# F1C100S-MY-.net
KiCad netlist of a schematic drawn in Altium Designer
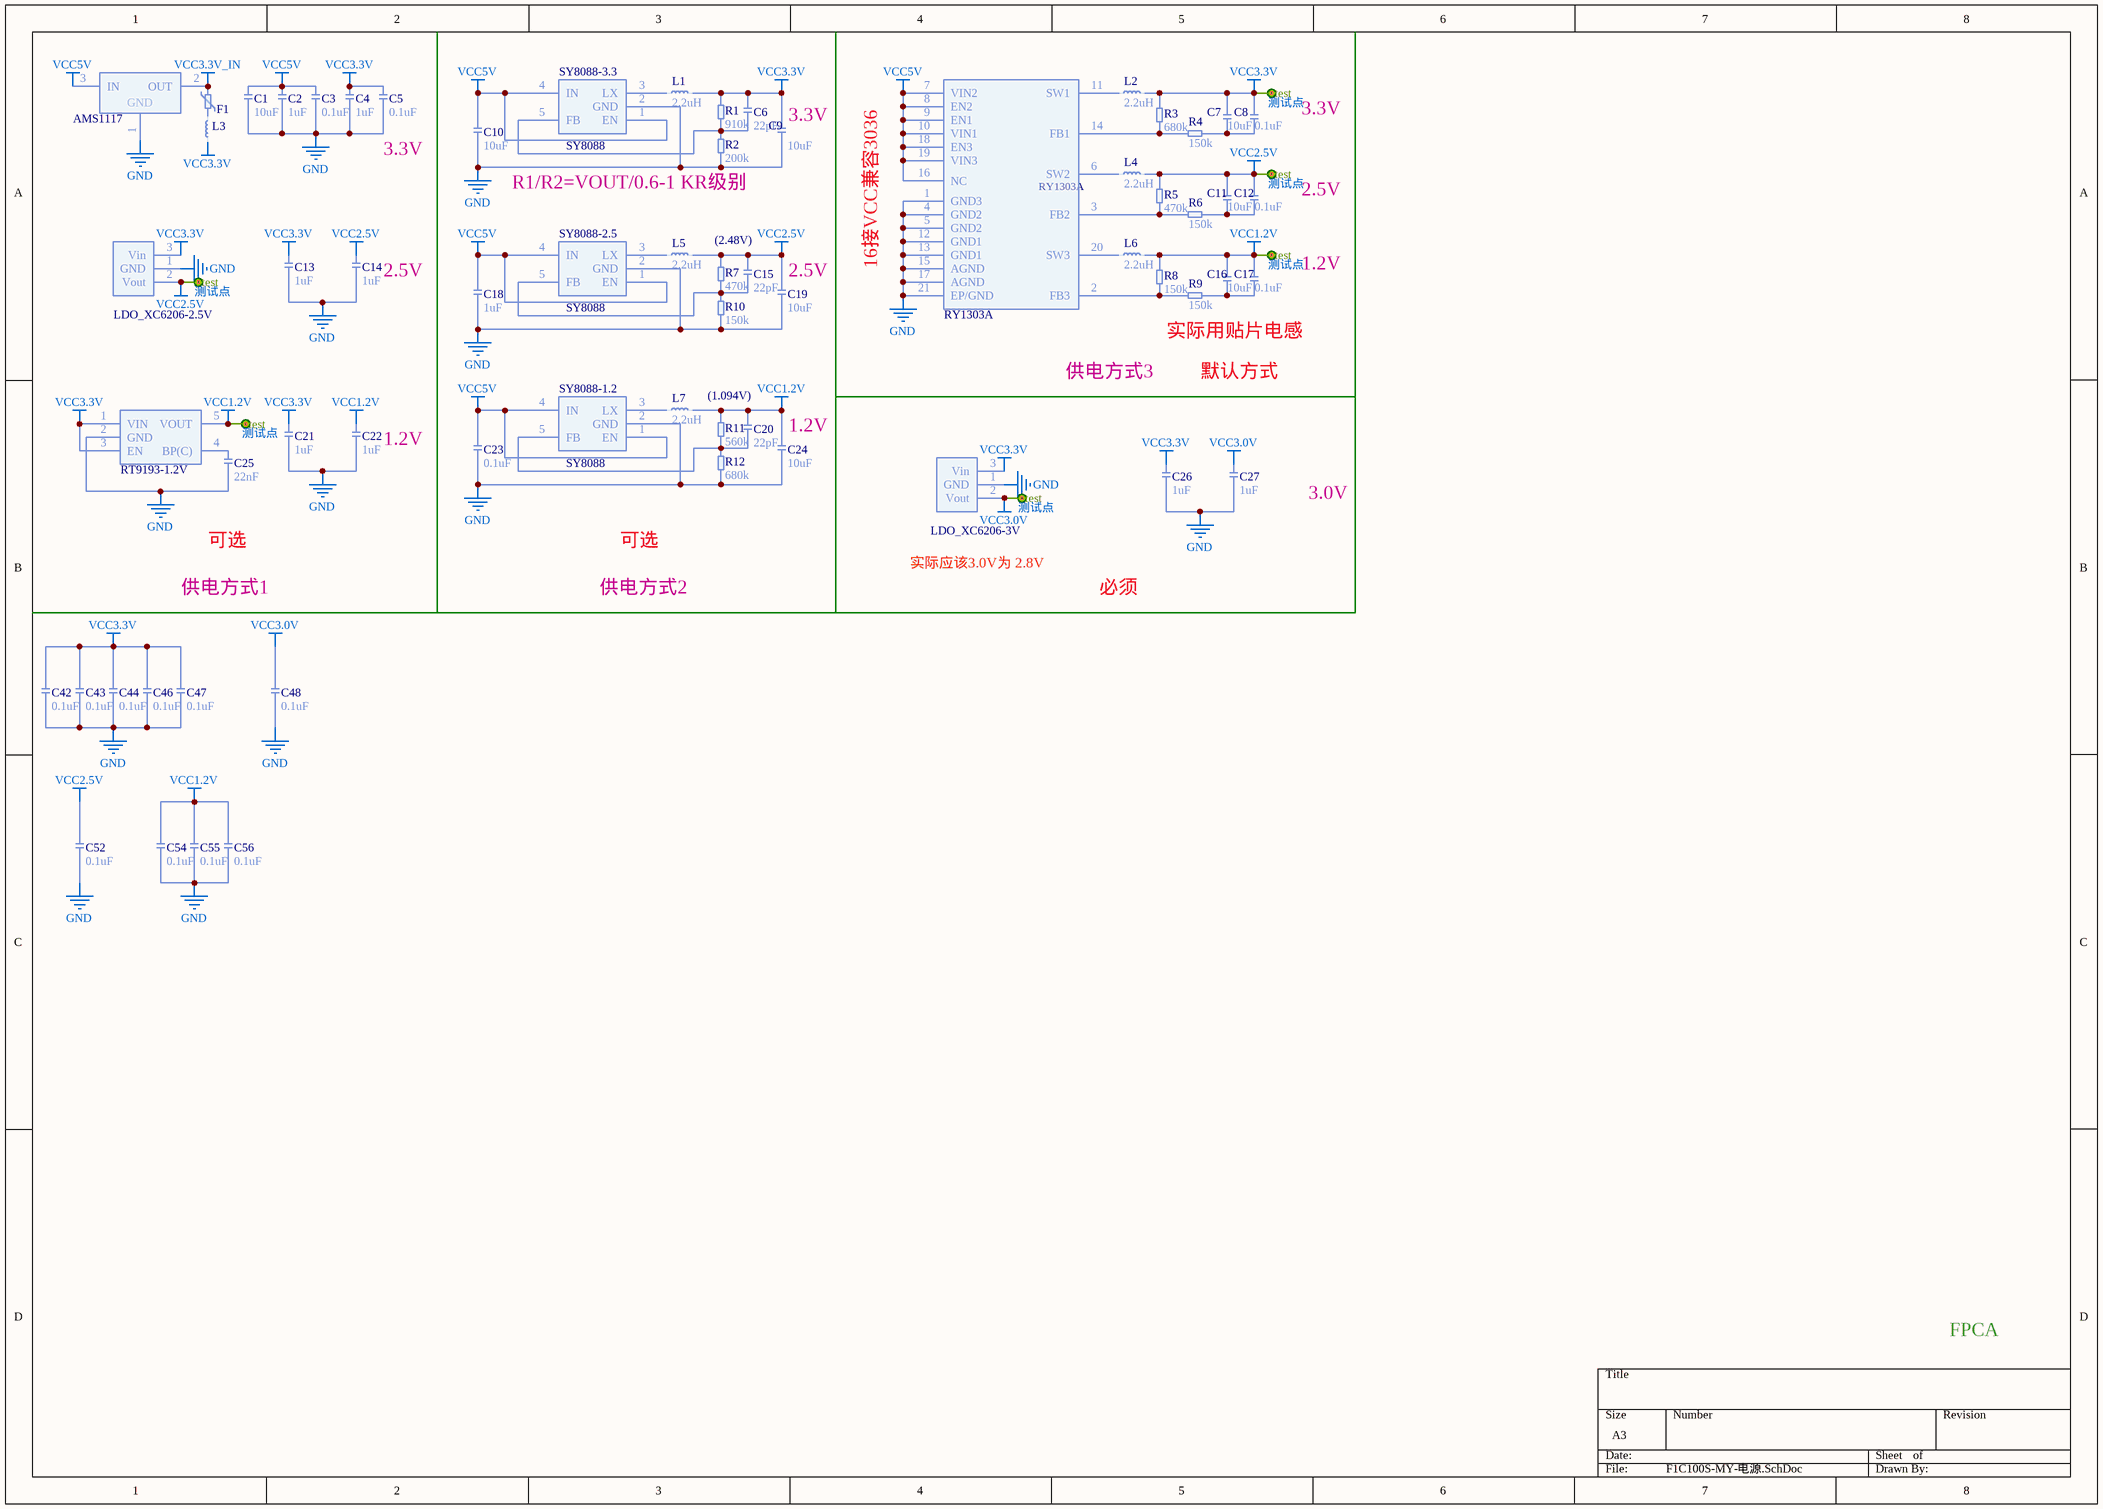
[diagram p0: F1C100S-MY-电源.SchDoc]

(export (version "E")
  (design (tool "Eeschema 10.0.6"))
  (components
    (comp (ref "AMS1117")
      (value "LDO_AMS1117")
      (footprint "SOT-89")
      (libsource (lib "常用芯片") (part "LDO_AMS1117"))
    )
    (comp (ref "C1")
      (value "10uF")
      (footprint "0805C-mini")
      (fields (field (name "Comment") "非极性电容"))
      (libsource (lib "电容") (part "非极性电容"))
    )
    (comp (ref "C2")
      (value "1uF")
      (footprint "0603C-mini")
      (fields (field (name "Comment") "非极性电容"))
      (libsource (lib "电容") (part "非极性电容"))
    )
    (comp (ref "C3")
      (value "0.1uF")
      (footprint "0603C-mini")
      (fields (field (name "Comment") "非极性电容"))
      (libsource (lib "电容") (part "非极性电容"))
    )
    (comp (ref "C4")
      (value "1uF")
      (footprint "0603C-mini")
      (fields (field (name "Comment") "非极性电容"))
      (libsource (lib "电容") (part "非极性电容"))
    )
    (comp (ref "C5")
      (value "0.1uF")
      (footprint "0603C-mini")
      (fields (field (name "Comment") "非极性电容"))
      (libsource (lib "电容") (part "非极性电容"))
    )
    (comp (ref "C6")
      (value "22pF")
      (footprint "0603C-mini")
      (fields (field (name "Comment") "非极性电容"))
      (libsource (lib "电容") (part "非极性电容"))
    )
    (comp (ref "C7")
      (value "10uF")
      (footprint "0805C-mini")
      (fields (field (name "Comment") "非极性电容"))
      (libsource (lib "电容") (part "非极性电容"))
    )
    (comp (ref "C8")
      (value "0.1uF")
      (footprint "0603C-mini")
      (fields (field (name "Comment") "非极性电容"))
      (libsource (lib "电容") (part "非极性电容"))
    )
    (comp (ref "C9")
      (value "10uF")
      (footprint "0805C-mini")
      (fields (field (name "Comment") "非极性电容"))
      (libsource (lib "电容") (part "非极性电容"))
    )
    (comp (ref "C10")
      (value "10uF")
      (footprint "0805C-mini")
      (fields (field (name "Comment") "非极性电容"))
      (libsource (lib "电容") (part "非极性电容"))
    )
    (comp (ref "C11")
      (value "10uF")
      (footprint "0805C-mini")
      (fields (field (name "Comment") "非极性电容"))
      (libsource (lib "电容") (part "非极性电容"))
    )
    (comp (ref "C12")
      (value "0.1uF")
      (footprint "0603C-mini")
      (fields (field (name "Comment") "非极性电容"))
      (libsource (lib "电容") (part "非极性电容"))
    )
    (comp (ref "C13")
      (value "1uF")
      (footprint "0603C-mini")
      (fields (field (name "Comment") "非极性电容"))
      (libsource (lib "电容") (part "非极性电容"))
    )
    (comp (ref "C14")
      (value "1uF")
      (footprint "0603C-mini")
      (fields (field (name "Comment") "非极性电容"))
      (libsource (lib "电容") (part "非极性电容"))
    )
    (comp (ref "C15")
      (value "22pF")
      (footprint "0603C-mini")
      (fields (field (name "Comment") "非极性电容"))
      (libsource (lib "电容") (part "非极性电容"))
    )
    (comp (ref "C16")
      (value "10uF")
      (footprint "0805C-mini")
      (fields (field (name "Comment") "非极性电容"))
      (libsource (lib "电容") (part "非极性电容"))
    )
    (comp (ref "C17")
      (value "0.1uF")
      (footprint "0603C-mini")
      (fields (field (name "Comment") "非极性电容"))
      (libsource (lib "电容") (part "非极性电容"))
    )
    (comp (ref "C18")
      (value "1uF")
      (footprint "0805C-mini")
      (fields (field (name "Comment") "非极性电容"))
      (libsource (lib "电容") (part "非极性电容"))
    )
    (comp (ref "C19")
      (value "10uF")
      (footprint "0805C-mini")
      (fields (field (name "Comment") "非极性电容"))
      (libsource (lib "电容") (part "非极性电容"))
    )
    (comp (ref "C20")
      (value "22pF")
      (footprint "0603C-mini")
      (fields (field (name "Comment") "非极性电容"))
      (libsource (lib "电容") (part "非极性电容"))
    )
    (comp (ref "C21")
      (value "1uF")
      (footprint "0603C-mini")
      (fields (field (name "Comment") "非极性电容"))
      (libsource (lib "电容") (part "非极性电容"))
    )
    (comp (ref "C22")
      (value "1uF")
      (footprint "0603C-mini")
      (fields (field (name "Comment") "非极性电容"))
      (libsource (lib "电容") (part "非极性电容"))
    )
    (comp (ref "C23")
      (value "0.1uF")
      (footprint "0805C-mini")
      (fields (field (name "Comment") "非极性电容"))
      (libsource (lib "电容") (part "非极性电容"))
    )
    (comp (ref "C24")
      (value "10uF")
      (footprint "0805C-mini")
      (fields (field (name "Comment") "非极性电容"))
      (libsource (lib "电容") (part "非极性电容"))
    )
    (comp (ref "C25")
      (value "22nF")
      (footprint "0603C-mini")
      (fields (field (name "Comment") "非极性电容"))
      (libsource (lib "电容") (part "非极性电容"))
    )
    (comp (ref "C26")
      (value "1uF")
      (footprint "0603C-mini")
      (fields (field (name "Comment") "非极性电容"))
      (libsource (lib "电容") (part "非极性电容"))
    )
    (comp (ref "C27")
      (value "1uF")
      (footprint "0603C-mini")
      (fields (field (name "Comment") "非极性电容"))
      (libsource (lib "电容") (part "非极性电容"))
    )
    (comp (ref "C42")
      (value "0.1uF")
      (footprint "0603C-mini")
      (fields (field (name "Comment") "非极性电容"))
      (libsource (lib "电容") (part "非极性电容"))
    )
    (comp (ref "C43")
      (value "0.1uF")
      (footprint "0603C-mini")
      (fields (field (name "Comment") "非极性电容"))
      (libsource (lib "电容") (part "非极性电容"))
    )
    (comp (ref "C44")
      (value "0.1uF")
      (footprint "0603C-mini")
      (fields (field (name "Comment") "非极性电容"))
      (libsource (lib "电容") (part "非极性电容"))
    )
    (comp (ref "C46")
      (value "0.1uF")
      (footprint "0603C-mini")
      (fields (field (name "Comment") "非极性电容"))
      (libsource (lib "电容") (part "非极性电容"))
    )
    (comp (ref "C47")
      (value "0.1uF")
      (footprint "0603C-mini")
      (fields (field (name "Comment") "非极性电容"))
      (libsource (lib "电容") (part "非极性电容"))
    )
    (comp (ref "C48")
      (value "0.1uF")
      (footprint "0603C-mini")
      (fields (field (name "Comment") "非极性电容"))
      (libsource (lib "电容") (part "非极性电容"))
    )
    (comp (ref "C52")
      (value "0.1uF")
      (footprint "0603C-mini")
      (fields (field (name "Comment") "非极性电容"))
      (libsource (lib "电容") (part "非极性电容"))
    )
    (comp (ref "C54")
      (value "0.1uF")
      (footprint "0603C-mini")
      (fields (field (name "Comment") "非极性电容"))
      (libsource (lib "电容") (part "非极性电容"))
    )
    (comp (ref "C55")
      (value "0.1uF")
      (footprint "0603C-mini")
      (fields (field (name "Comment") "非极性电容"))
      (libsource (lib "电容") (part "非极性电容"))
    )
    (comp (ref "C56")
      (value "0.1uF")
      (footprint "0603C-mini")
      (fields (field (name "Comment") "非极性电容"))
      (libsource (lib "电容") (part "非极性电容"))
    )
    (comp (ref "F1") (value "自恢复保险丝") (footprint "电阻:FU 0603") (libsource (lib "电阻") (part "自恢复保险丝")))
    (comp (ref "L1")
      (value "2.2uH")
      (footprint "SMD-4.5x4.0x3.2mm")
      (fields (field (name "Comment") "贴片电感"))
      (libsource (lib "电感") (part "贴片电感"))
    )
    (comp (ref "L2")
      (value "2.2uH")
      (footprint "SMD-4.5x4.0x3.2mm")
      (fields (field (name "Comment") "贴片电感"))
      (libsource (lib "电感") (part "贴片电感"))
    )
    (comp (ref "L3") (value "磁珠") (footprint "0805C") (libsource (lib "电感") (part "磁珠")))
    (comp (ref "L4")
      (value "2.2uH")
      (footprint "SMD-4.5x4.0x3.2mm")
      (fields (field (name "Comment") "贴片电感"))
      (libsource (lib "电感") (part "贴片电感"))
    )
    (comp (ref "L5")
      (value "2.2uH")
      (footprint "SMD-4.5x4.0x3.2mm")
      (fields (field (name "Comment") "贴片电感"))
      (libsource (lib "电感") (part "贴片电感"))
    )
    (comp (ref "L6")
      (value "2.2uH")
      (footprint "SMD-4.5x4.0x3.2mm")
      (fields (field (name "Comment") "贴片电感"))
      (libsource (lib "电感") (part "贴片电感"))
    )
    (comp (ref "L7")
      (value "2.2uH")
      (footprint "SMD-4.5x4.0x3.2mm")
      (fields (field (name "Comment") "贴片电感"))
      (libsource (lib "电感") (part "贴片电感"))
    )
    (comp (ref "LDO_XC6206-2.5V")
      (value "LDO_XC6206-SOT-23")
      (footprint "SOT-23")
      (libsource (lib "常用芯片") (part "LDO_XC6206-SOT-23"))
    )
    (comp (ref "LDO_XC6206-3V")
      (value "LDO_XC6206-SOT-23")
      (footprint "SOT-23")
      (libsource (lib "常用芯片") (part "LDO_XC6206-SOT-23"))
    )
    (comp (ref "R1")
      (value "910k")
      (footprint "R0603-mini")
      (description "贴片电阻")
      (libsource (lib "电阻") (part "贴片电阻"))
    )
    (comp (ref "R2")
      (value "200k")
      (footprint "R0603-mini")
      (description "贴片电阻")
      (libsource (lib "电阻") (part "贴片电阻"))
    )
    (comp (ref "R3")
      (value "680k")
      (footprint "R0603-mini")
      (description "贴片电阻")
      (libsource (lib "电阻") (part "贴片电阻"))
    )
    (comp (ref "R4")
      (value "150k")
      (footprint "R0603-mini")
      (description "贴片电阻")
      (libsource (lib "") (part "贴片电阻_1"))
    )
    (comp (ref "R5")
      (value "470k")
      (footprint "R0603-mini")
      (description "贴片电阻")
      (libsource (lib "电阻") (part "贴片电阻"))
    )
    (comp (ref "R6")
      (value "150k")
      (footprint "R0603-mini")
      (description "贴片电阻")
      (libsource (lib "") (part "贴片电阻_1"))
    )
    (comp (ref "R7")
      (value "470k")
      (footprint "R0603-mini")
      (description "贴片电阻")
      (libsource (lib "电阻") (part "贴片电阻"))
    )
    (comp (ref "R8")
      (value "150k")
      (footprint "R0603-mini")
      (description "贴片电阻")
      (libsource (lib "电阻") (part "贴片电阻"))
    )
    (comp (ref "R9")
      (value "150k")
      (footprint "R0603-mini")
      (description "贴片电阻")
      (libsource (lib "") (part "贴片电阻_1"))
    )
    (comp (ref "R10")
      (value "150k")
      (footprint "R0603-mini")
      (description "贴片电阻")
      (libsource (lib "电阻") (part "贴片电阻"))
    )
    (comp (ref "R11")
      (value "560k")
      (footprint "R0603-mini")
      (description "贴片电阻")
      (libsource (lib "电阻") (part "贴片电阻"))
    )
    (comp (ref "R12")
      (value "680k")
      (footprint "R0603-mini")
      (description "贴片电阻")
      (libsource (lib "电阻") (part "贴片电阻"))
    )
    (comp (ref "RT9193-1.2V")
      (value "LDO_RT9193")
      (footprint "sot-23-5")
      (description "300ma 1.2V LDO")
      (libsource (lib "常用芯片") (part "LDO_RT9193"))
    )
    (comp (ref "RY1303A")
      (value "RY1303A-?")
      (footprint "QFN-20")
      (description "2A")
      (libsource (lib "常用芯片") (part "DCDC_RY1303A"))
    )
    (comp (ref "SY8088-1.2")
      (value "SY8088")
      (footprint "SOT-23-5")
      (libsource (lib "常用芯片") (part "DCDC_SY8088AAC"))
    )
    (comp (ref "SY8088-2.5")
      (value "SY8088")
      (footprint "SOT-23-5")
      (libsource (lib "常用芯片") (part "DCDC_SY8088AAC"))
    )
    (comp (ref "SY8088-3.3")
      (value "SY8088")
      (footprint "SOT-23-5")
      (libsource (lib "常用芯片") (part "DCDC_SY8088AAC"))
    )
    (comp (ref "test1") (value "测试点") (footprint "测试点30mil") (libsource (lib "接插件") (part "测试点")))
    (comp (ref "test2") (value "测试点") (footprint "测试点30mil") (libsource (lib "接插件") (part "测试点")))
    (comp (ref "test3") (value "测试点") (footprint "测试点30mil") (libsource (lib "接插件") (part "测试点")))
    (comp (ref "test4") (value "测试点") (footprint "测试点30mil") (libsource (lib "接插件") (part "测试点")))
    (comp (ref "test5") (value "测试点") (footprint "测试点30mil") (libsource (lib "接插件") (part "测试点")))
    (comp (ref "test6") (value "测试点") (footprint "测试点30mil") (libsource (lib "接插件") (part "测试点")))
  )
  (nets
    (net (code "2") (name "GND") (class "Default")
      (node (ref "AMS1117") (pin "1") (pinfunction "GND_1") (pintype "power_in"))
      (node (ref "C1") (pin "2") (pinfunction "2_2") (pintype "passive"))
      (node (ref "C10") (pin "2") (pinfunction "2_2") (pintype "passive"))
      (node (ref "C13") (pin "1") (pinfunction "1_1") (pintype "passive"))
      (node (ref "C14") (pin "1") (pinfunction "1_1") (pintype "passive"))
      (node (ref "C18") (pin "2") (pinfunction "2_2") (pintype "passive"))
      (node (ref "C19") (pin "2") (pinfunction "2_2") (pintype "passive"))
      (node (ref "C2") (pin "2") (pinfunction "2_2") (pintype "passive"))
      (node (ref "C21") (pin "2") (pinfunction "2_2") (pintype "passive"))
      (node (ref "C22") (pin "1") (pinfunction "1_1") (pintype "passive"))
      (node (ref "C23") (pin "2") (pinfunction "2_2") (pintype "passive"))
      (node (ref "C24") (pin "2") (pinfunction "2_2") (pintype "passive"))
      (node (ref "C25") (pin "2") (pinfunction "2_2") (pintype "passive"))
      (node (ref "C26") (pin "1") (pinfunction "1_1") (pintype "passive"))
      (node (ref "C27") (pin "1") (pinfunction "1_1") (pintype "passive"))
      (node (ref "C3") (pin "2") (pinfunction "2_2") (pintype "passive"))
      (node (ref "C4") (pin "2") (pinfunction "2_2") (pintype "passive"))
      (node (ref "C42") (pin "1") (pinfunction "1_1") (pintype "passive"))
      (node (ref "C43") (pin "1") (pinfunction "1_1") (pintype "passive"))
      (node (ref "C44") (pin "1") (pinfunction "1_1") (pintype "passive"))
      (node (ref "C46") (pin "1") (pinfunction "1_1") (pintype "passive"))
      (node (ref "C47") (pin "2") (pinfunction "2_2") (pintype "passive"))
      (node (ref "C48") (pin "1") (pinfunction "1_1") (pintype "passive"))
      (node (ref "C5") (pin "2") (pinfunction "2_2") (pintype "passive"))
      (node (ref "C52") (pin "1") (pinfunction "1_1") (pintype "passive"))
      (node (ref "C54") (pin "1") (pinfunction "1_1") (pintype "passive"))
      (node (ref "C55") (pin "1") (pinfunction "1_1") (pintype "passive"))
      (node (ref "C56") (pin "1") (pinfunction "1_1") (pintype "passive"))
      (node (ref "C9") (pin "2") (pinfunction "2_2") (pintype "passive"))
      (node (ref "LDO_XC6206-2.5V") (pin "1") (pinfunction "GND_1") (pintype "passive"))
      (node (ref "LDO_XC6206-3V") (pin "1") (pinfunction "GND_1") (pintype "passive"))
      (node (ref "R10") (pin "1") (pinfunction "1_1") (pintype "passive"))
      (node (ref "R12") (pin "1") (pinfunction "1_1") (pintype "passive"))
      (node (ref "R2") (pin "1") (pinfunction "1_1") (pintype "passive"))
      (node (ref "RT9193-1.2V") (pin "2") (pinfunction "GND_2") (pintype "passive"))
      (node (ref "RY1303A") (pin "1") (pinfunction "GND3_1") (pintype "passive"))
      (node (ref "RY1303A") (pin "12") (pinfunction "GND1_12") (pintype "passive"))
      (node (ref "RY1303A") (pin "13") (pinfunction "GND1_13") (pintype "passive"))
      (node (ref "RY1303A") (pin "15") (pinfunction "AGND_15") (pintype "passive"))
      (node (ref "RY1303A") (pin "17") (pinfunction "AGND_17") (pintype "passive"))
      (node (ref "RY1303A") (pin "21") (pinfunction "EP/GND_21") (pintype "passive"))
      (node (ref "RY1303A") (pin "4") (pinfunction "GND2_4") (pintype "passive"))
      (node (ref "RY1303A") (pin "5") (pinfunction "GND2_5") (pintype "passive"))
      (node (ref "SY8088-1.2") (pin "2") (pinfunction "GND_2") (pintype "power_in"))
      (node (ref "SY8088-2.5") (pin "2") (pinfunction "GND_2") (pintype "power_in"))
      (node (ref "SY8088-3.3") (pin "2") (pinfunction "GND_2") (pintype "power_in"))
    )
    (net (code "3") (name "Net-(C7-Pad2)") (class "Default")
      (node (ref "C7") (pin "2") (pinfunction "2_2") (pintype "passive"))
      (node (ref "C8") (pin "2") (pinfunction "2_2") (pintype "passive"))
      (node (ref "R4") (pin "1") (pinfunction "1_1") (pintype "passive"))
    )
    (net (code "4") (name "Net-(C11-Pad2)") (class "Default")
      (node (ref "C11") (pin "2") (pinfunction "2_2") (pintype "passive"))
      (node (ref "C12") (pin "2") (pinfunction "2_2") (pintype "passive"))
      (node (ref "R6") (pin "1") (pinfunction "1_1") (pintype "passive"))
    )
    (net (code "5") (name "Net-(C16-Pad2)") (class "Default")
      (node (ref "C16") (pin "2") (pinfunction "2_2") (pintype "passive"))
      (node (ref "C17") (pin "2") (pinfunction "2_2") (pintype "passive"))
      (node (ref "R9") (pin "1") (pinfunction "1_1") (pintype "passive"))
    )
    (net (code "6") (name "Net-(F1-Pad1)") (class "Default")
      (node (ref "F1") (pin "1") (pinfunction "1_1") (pintype "passive"))
      (node (ref "L3") (pin "2") (pinfunction "2_2") (pintype "passive"))
    )
    (net (code "7") (name "Net-(RT9193-1.2V-BP(C))") (class "Default")
      (node (ref "C25") (pin "1") (pinfunction "1_1") (pintype "passive"))
      (node (ref "RT9193-1.2V") (pin "4") (pinfunction "BP(C)_4") (pintype "passive"))
    )
    (net (code "8") (name "Net-(RY1303A-FB1)") (class "Default")
      (node (ref "R3") (pin "1") (pinfunction "1_1") (pintype "passive"))
      (node (ref "R4") (pin "2") (pinfunction "2_2") (pintype "passive"))
      (node (ref "RY1303A") (pin "14") (pinfunction "FB1_14") (pintype "passive"))
    )
    (net (code "9") (name "Net-(RY1303A-FB2)") (class "Default")
      (node (ref "R5") (pin "1") (pinfunction "1_1") (pintype "passive"))
      (node (ref "R6") (pin "2") (pinfunction "2_2") (pintype "passive"))
      (node (ref "RY1303A") (pin "3") (pinfunction "FB2_3") (pintype "passive"))
    )
    (net (code "10") (name "Net-(RY1303A-FB3)") (class "Default")
      (node (ref "R8") (pin "1") (pinfunction "1_1") (pintype "passive"))
      (node (ref "R9") (pin "2") (pinfunction "2_2") (pintype "passive"))
      (node (ref "RY1303A") (pin "2") (pinfunction "FB3_2") (pintype "passive"))
    )
    (net (code "11") (name "Net-(RY1303A-SW1)") (class "Default")
      (node (ref "L2") (pin "1") (pinfunction "1_1") (pintype "passive"))
      (node (ref "RY1303A") (pin "11") (pinfunction "SW1_11") (pintype "passive"))
    )
    (net (code "12") (name "Net-(RY1303A-SW2)") (class "Default")
      (node (ref "L4") (pin "1") (pinfunction "1_1") (pintype "passive"))
      (node (ref "RY1303A") (pin "6") (pinfunction "SW2_6") (pintype "passive"))
    )
    (net (code "13") (name "Net-(RY1303A-SW3)") (class "Default")
      (node (ref "L6") (pin "1") (pinfunction "1_1") (pintype "passive"))
      (node (ref "RY1303A") (pin "20") (pinfunction "SW3_20") (pintype "passive"))
    )
    (net (code "14") (name "Net-(SY8088-1.2-FB)") (class "Default")
      (node (ref "C20") (pin "2") (pinfunction "2_2") (pintype "passive"))
      (node (ref "R11") (pin "1") (pinfunction "1_1") (pintype "passive"))
      (node (ref "R12") (pin "2") (pinfunction "2_2") (pintype "passive"))
      (node (ref "SY8088-1.2") (pin "5") (pinfunction "FB_5") (pintype "passive"))
    )
    (net (code "15") (name "Net-(SY8088-1.2-LX)") (class "Default")
      (node (ref "L7") (pin "1") (pinfunction "1_1") (pintype "passive"))
      (node (ref "SY8088-1.2") (pin "3") (pinfunction "LX_3") (pintype "power_in"))
    )
    (net (code "16") (name "Net-(SY8088-2.5-FB)") (class "Default")
      (node (ref "C15") (pin "2") (pinfunction "2_2") (pintype "passive"))
      (node (ref "R10") (pin "2") (pinfunction "2_2") (pintype "passive"))
      (node (ref "R7") (pin "1") (pinfunction "1_1") (pintype "passive"))
      (node (ref "SY8088-2.5") (pin "5") (pinfunction "FB_5") (pintype "passive"))
    )
    (net (code "17") (name "Net-(SY8088-2.5-LX)") (class "Default")
      (node (ref "L5") (pin "1") (pinfunction "1_1") (pintype "passive"))
      (node (ref "SY8088-2.5") (pin "3") (pinfunction "LX_3") (pintype "power_in"))
    )
    (net (code "18") (name "Net-(SY8088-3.3-FB)") (class "Default")
      (node (ref "C6") (pin "2") (pinfunction "2_2") (pintype "passive"))
      (node (ref "R1") (pin "1") (pinfunction "1_1") (pintype "passive"))
      (node (ref "R2") (pin "2") (pinfunction "2_2") (pintype "passive"))
      (node (ref "SY8088-3.3") (pin "5") (pinfunction "FB_5") (pintype "passive"))
    )
    (net (code "19") (name "Net-(SY8088-3.3-LX)") (class "Default")
      (node (ref "L1") (pin "1") (pinfunction "1_1") (pintype "passive"))
      (node (ref "SY8088-3.3") (pin "3") (pinfunction "LX_3") (pintype "power_in"))
    )
    (net (code "20") (name "VCC1.2V") (class "Default")
      (node (ref "C16") (pin "1") (pinfunction "1_1") (pintype "passive"))
      (node (ref "C17") (pin "1") (pinfunction "1_1") (pintype "passive"))
      (node (ref "C20") (pin "1") (pinfunction "1_1") (pintype "passive"))
      (node (ref "C22") (pin "2") (pinfunction "2_2") (pintype "passive"))
      (node (ref "C24") (pin "1") (pinfunction "1_1") (pintype "passive"))
      (node (ref "C54") (pin "2") (pinfunction "2_2") (pintype "passive"))
      (node (ref "C55") (pin "2") (pinfunction "2_2") (pintype "passive"))
      (node (ref "C56") (pin "2") (pinfunction "2_2") (pintype "passive"))
      (node (ref "L6") (pin "2") (pinfunction "2_2") (pintype "passive"))
      (node (ref "L7") (pin "2") (pinfunction "2_2") (pintype "passive"))
      (node (ref "R11") (pin "2") (pinfunction "2_2") (pintype "passive"))
      (node (ref "R8") (pin "2") (pinfunction "2_2") (pintype "passive"))
      (node (ref "RT9193-1.2V") (pin "5") (pinfunction "VOUT_5") (pintype "passive"))
      (node (ref "test3") (pin "1") (pinfunction "test_1") (pintype "passive"))
      (node (ref "test5") (pin "1") (pinfunction "test_1") (pintype "passive"))
    )
    (net (code "21") (name "VCC2.5V") (class "Default")
      (node (ref "C11") (pin "1") (pinfunction "1_1") (pintype "passive"))
      (node (ref "C12") (pin "1") (pinfunction "1_1") (pintype "passive"))
      (node (ref "C14") (pin "2") (pinfunction "2_2") (pintype "passive"))
      (node (ref "C15") (pin "1") (pinfunction "1_1") (pintype "passive"))
      (node (ref "C19") (pin "1") (pinfunction "1_1") (pintype "passive"))
      (node (ref "C52") (pin "2") (pinfunction "2_2") (pintype "passive"))
      (node (ref "L4") (pin "2") (pinfunction "2_2") (pintype "passive"))
      (node (ref "L5") (pin "2") (pinfunction "2_2") (pintype "passive"))
      (node (ref "LDO_XC6206-2.5V") (pin "2") (pinfunction "Vout_2") (pintype "passive"))
      (node (ref "R5") (pin "2") (pinfunction "2_2") (pintype "passive"))
      (node (ref "R7") (pin "2") (pinfunction "2_2") (pintype "passive"))
      (node (ref "test2") (pin "1") (pinfunction "test_1") (pintype "passive"))
      (node (ref "test4") (pin "1") (pinfunction "test_1") (pintype "passive"))
    )
    (net (code "22") (name "VCC3.0V") (class "Default")
      (node (ref "C27") (pin "2") (pinfunction "2_2") (pintype "passive"))
      (node (ref "C48") (pin "2") (pinfunction "2_2") (pintype "passive"))
      (node (ref "LDO_XC6206-3V") (pin "2") (pinfunction "Vout_2") (pintype "passive"))
      (node (ref "test6") (pin "1") (pinfunction "test_1") (pintype "passive"))
    )
    (net (code "23") (name "VCC3.3V") (class "Default")
      (node (ref "C13") (pin "2") (pinfunction "2_2") (pintype "passive"))
      (node (ref "C21") (pin "1") (pinfunction "1_1") (pintype "passive"))
      (node (ref "C26") (pin "2") (pinfunction "2_2") (pintype "passive"))
      (node (ref "C4") (pin "1") (pinfunction "1_1") (pintype "passive"))
      (node (ref "C42") (pin "2") (pinfunction "2_2") (pintype "passive"))
      (node (ref "C43") (pin "2") (pinfunction "2_2") (pintype "passive"))
      (node (ref "C44") (pin "2") (pinfunction "2_2") (pintype "passive"))
      (node (ref "C46") (pin "2") (pinfunction "2_2") (pintype "passive"))
      (node (ref "C47") (pin "1") (pinfunction "1_1") (pintype "passive"))
      (node (ref "C5") (pin "1") (pinfunction "1_1") (pintype "passive"))
      (node (ref "C6") (pin "1") (pinfunction "1_1") (pintype "passive"))
      (node (ref "C7") (pin "1") (pinfunction "1_1") (pintype "passive"))
      (node (ref "C8") (pin "1") (pinfunction "1_1") (pintype "passive"))
      (node (ref "C9") (pin "1") (pinfunction "1_1") (pintype "passive"))
      (node (ref "L1") (pin "2") (pinfunction "2_2") (pintype "passive"))
      (node (ref "L2") (pin "2") (pinfunction "2_2") (pintype "passive"))
      (node (ref "L3") (pin "1") (pinfunction "1_1") (pintype "passive"))
      (node (ref "LDO_XC6206-2.5V") (pin "3") (pinfunction "Vin_3") (pintype "passive"))
      (node (ref "LDO_XC6206-3V") (pin "3") (pinfunction "Vin_3") (pintype "passive"))
      (node (ref "R1") (pin "2") (pinfunction "2_2") (pintype "passive"))
      (node (ref "R3") (pin "2") (pinfunction "2_2") (pintype "passive"))
      (node (ref "RT9193-1.2V") (pin "1") (pinfunction "VIN_1") (pintype "passive"))
      (node (ref "RT9193-1.2V") (pin "3") (pinfunction "EN_3") (pintype "passive"))
      (node (ref "test1") (pin "1") (pinfunction "test_1") (pintype "passive"))
    )
    (net (code "24") (name "VCC3.3V_IN") (class "Default")
      (node (ref "AMS1117") (pin "2") (pinfunction "OUT_2") (pintype "power_in"))
      (node (ref "F1") (pin "2") (pinfunction "2_2") (pintype "passive"))
    )
    (net (code "25") (name "VCC5V") (class "Default")
      (node (ref "AMS1117") (pin "3") (pinfunction "IN_3") (pintype "power_in"))
      (node (ref "C1") (pin "1") (pinfunction "1_1") (pintype "passive"))
      (node (ref "C10") (pin "1") (pinfunction "1_1") (pintype "passive"))
      (node (ref "C18") (pin "1") (pinfunction "1_1") (pintype "passive"))
      (node (ref "C2") (pin "1") (pinfunction "1_1") (pintype "passive"))
      (node (ref "C23") (pin "1") (pinfunction "1_1") (pintype "passive"))
      (node (ref "C3") (pin "1") (pinfunction "1_1") (pintype "passive"))
      (node (ref "RY1303A") (pin "10") (pinfunction "VIN1_10") (pintype "passive"))
      (node (ref "RY1303A") (pin "16") (pinfunction "NC_16") (pintype "passive"))
      (node (ref "RY1303A") (pin "18") (pinfunction "EN3_18") (pintype "passive"))
      (node (ref "RY1303A") (pin "19") (pinfunction "VIN3_19") (pintype "passive"))
      (node (ref "RY1303A") (pin "7") (pinfunction "VIN2_7") (pintype "passive"))
      (node (ref "RY1303A") (pin "8") (pinfunction "EN2_8") (pintype "passive"))
      (node (ref "RY1303A") (pin "9") (pinfunction "EN1_9") (pintype "passive"))
      (node (ref "SY8088-1.2") (pin "1") (pinfunction "EN_1") (pintype "passive"))
      (node (ref "SY8088-1.2") (pin "4") (pinfunction "IN_4") (pintype "power_in"))
      (node (ref "SY8088-2.5") (pin "1") (pinfunction "EN_1") (pintype "passive"))
      (node (ref "SY8088-2.5") (pin "4") (pinfunction "IN_4") (pintype "power_in"))
      (node (ref "SY8088-3.3") (pin "1") (pinfunction "EN_1") (pintype "passive"))
      (node (ref "SY8088-3.3") (pin "4") (pinfunction "IN_4") (pintype "power_in"))
    )
  )
)
